# Surf5_R110.net
KiCad netlist of a schematic drawn in Altium Designer
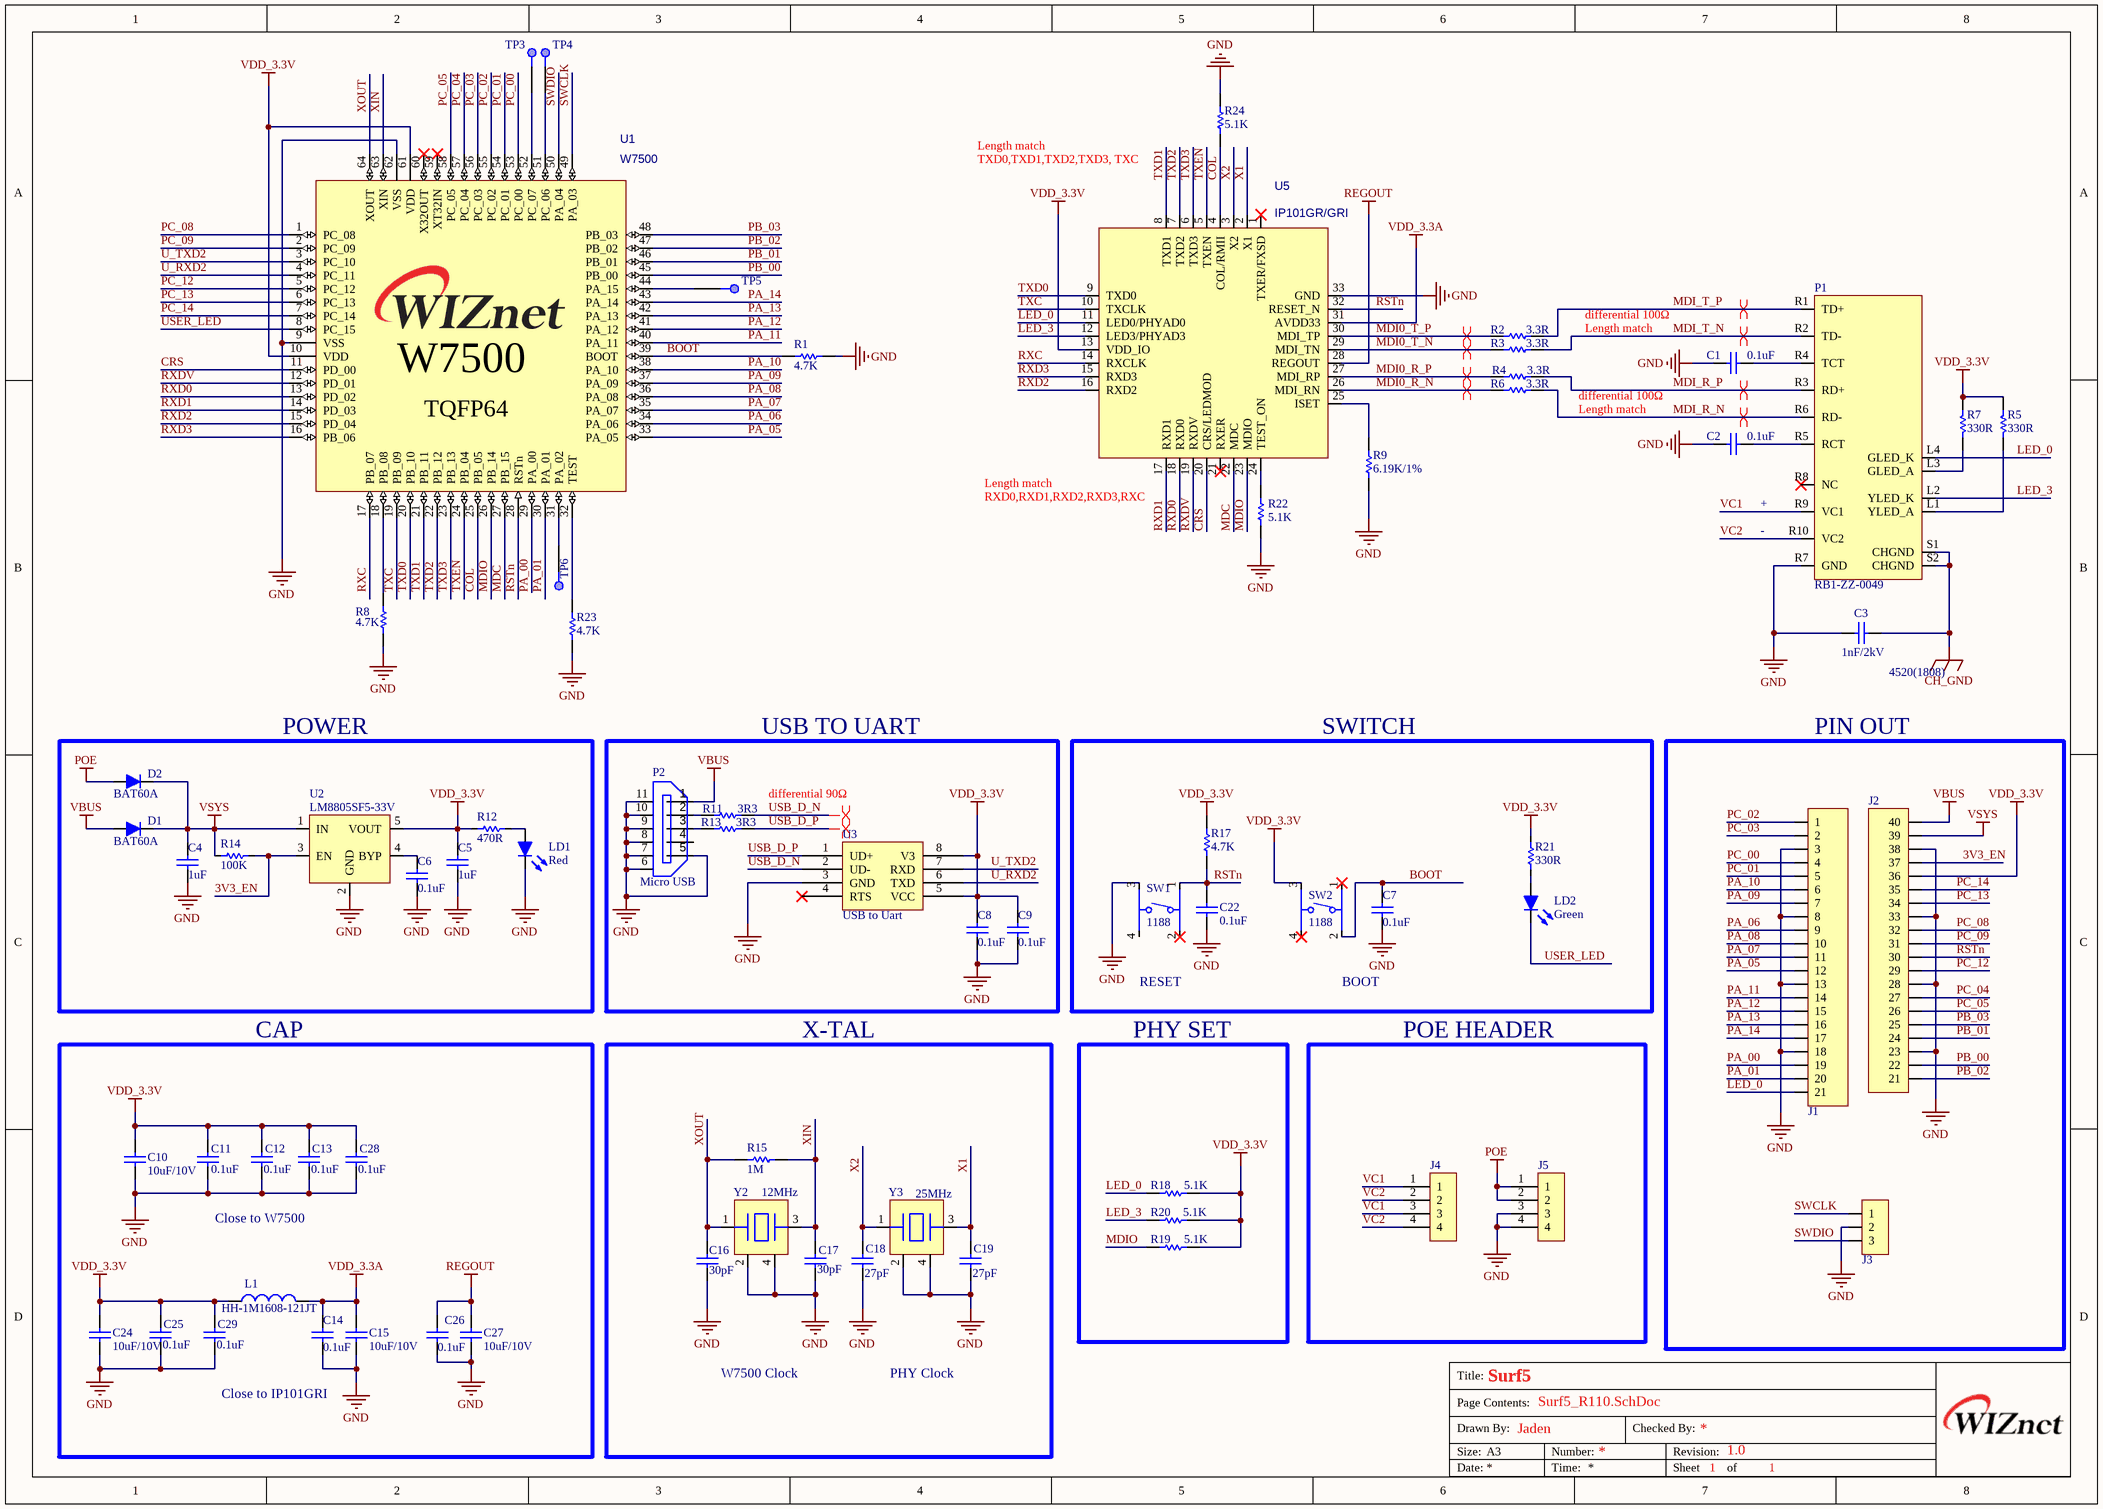
[diagram p0: Surf5_R110.SchDoc]

(export (version "E")
  (design (tool "Eeschema 10.0.6"))
  (components
    (comp (ref "C1")
      (value "0.1uF")
      (footprint "CAP-0402")
      (description "Ceramic CAP 0402(1005)")
      (libsource (lib "Scott_lib") (part "CAP-0402"))
    )
    (comp (ref "C2")
      (value "0.1uF")
      (footprint "CAP-0402")
      (description "Ceramic CAP 0402(1005)")
      (libsource (lib "Scott_lib") (part "CAP-0402"))
    )
    (comp (ref "C3")
      (value "1nF/2kV")
      (footprint "CAP-1808")
      (description "Ceramic CAP 1808(4520)")
      (libsource (lib "Scott_lib") (part "CAP-1808"))
    )
    (comp (ref "C4")
      (value "1uF")
      (footprint "CAP-0402")
      (description "Ceramic CAP 0402(1005)")
      (libsource (lib "Scott_lib") (part "CAP-0402"))
    )
    (comp (ref "C5")
      (value "1uF")
      (footprint "CAP-0402")
      (description "Ceramic CAP 0402(1005)")
      (libsource (lib "Scott_lib") (part "CAP-0402"))
    )
    (comp (ref "C6")
      (value "0.1uF")
      (footprint "CAP-0402")
      (description "Ceramic CAP 0402(1005)")
      (libsource (lib "Scott_lib") (part "CAP-0402"))
    )
    (comp (ref "C7")
      (value "0.1uF")
      (footprint "CAP-0402")
      (description "Ceramic CAP 0402(1005)")
      (libsource (lib "Scott_lib") (part "CAP-0402"))
    )
    (comp (ref "C8")
      (value "0.1uF")
      (footprint "CAP-0402")
      (description "Ceramic CAP 0402(1005)")
      (libsource (lib "Scott_lib") (part "CAP-0402"))
    )
    (comp (ref "C9")
      (value "0.1uF")
      (footprint "CAP-0402")
      (description "Ceramic CAP 0402(1005)")
      (libsource (lib "Scott_lib") (part "CAP-0402"))
    )
    (comp (ref "C10")
      (value "10uF/10V")
      (footprint "Surf5_R110:CAP-0805-3")
      (description "MLCC-0805(2012)")
      (libsource (lib "Surf5_R110") (part "CAP-0805"))
    )
    (comp (ref "C11")
      (value "0.1uF")
      (footprint "CAP-0402")
      (description "Ceramic CAP 0402(1005)")
      (libsource (lib "Scott_lib") (part "CAP-0402"))
    )
    (comp (ref "C12")
      (value "0.1uF")
      (footprint "CAP-0402")
      (description "Ceramic CAP 0402(1005)")
      (libsource (lib "Scott_lib") (part "CAP-0402"))
    )
    (comp (ref "C13")
      (value "0.1uF")
      (footprint "CAP-0402")
      (description "Ceramic CAP 0402(1005)")
      (libsource (lib "Scott_lib") (part "CAP-0402"))
    )
    (comp (ref "C14")
      (value "0.1uF")
      (footprint "CAP-0402")
      (description "Ceramic CAP 0402(1005)")
      (libsource (lib "Scott_lib") (part "CAP-0402"))
    )
    (comp (ref "C15")
      (value "10uF/10V")
      (footprint "Surf5_R110:CAP-0805-3")
      (description "MLCC-0805(2012)")
      (libsource (lib "Surf5_R110") (part "CAP-0805"))
    )
    (comp (ref "C16")
      (value "30pF")
      (footprint "CAP-0402")
      (description "Ceramic CAP 0402(1005)")
      (libsource (lib "Scott_lib") (part "CAP-0402"))
    )
    (comp (ref "C17")
      (value "30pF")
      (footprint "CAP-0402")
      (description "Ceramic CAP 0402(1005)")
      (libsource (lib "Scott_lib") (part "CAP-0402"))
    )
    (comp (ref "C18")
      (value "27pF")
      (footprint "CAP-0402")
      (description "Ceramic CAP 0402(1005)")
      (libsource (lib "Scott_lib") (part "CAP-0402"))
    )
    (comp (ref "C19")
      (value "27pF")
      (footprint "CAP-0402")
      (description "Ceramic CAP 0402(1005)")
      (libsource (lib "Scott_lib") (part "CAP-0402"))
    )
    (comp (ref "C22")
      (value "0.1uF")
      (footprint "CAP-0402")
      (description "Ceramic CAP 0402(1005)")
      (libsource (lib "Scott_lib") (part "CAP-0402"))
    )
    (comp (ref "C24")
      (value "10uF/10V")
      (footprint "Surf5_R110:CAP-0805-3")
      (description "MLCC-0805(2012)")
      (libsource (lib "Surf5_R110") (part "CAP-0805"))
    )
    (comp (ref "C25")
      (value "0.1uF")
      (footprint "CAP-0402")
      (description "Ceramic CAP 0402(1005)")
      (libsource (lib "Scott_lib") (part "CAP-0402"))
    )
    (comp (ref "C26")
      (value "0.1uF")
      (footprint "CAP-0402")
      (description "Ceramic CAP 0402(1005)")
      (libsource (lib "Scott_lib") (part "CAP-0402"))
    )
    (comp (ref "C27")
      (value "10uF/10V")
      (footprint "Surf5_R110:CAP-0805-3")
      (description "MLCC-0805(2012)")
      (libsource (lib "Surf5_R110") (part "CAP-0805"))
    )
    (comp (ref "C28")
      (value "0.1uF")
      (footprint "CAP-0402")
      (description "Ceramic CAP 0402(1005)")
      (libsource (lib "Scott_lib") (part "CAP-0402"))
    )
    (comp (ref "C29")
      (value "0.1uF")
      (footprint "CAP-0402")
      (description "Ceramic CAP 0402(1005)")
      (libsource (lib "Scott_lib") (part "CAP-0402"))
    )
    (comp (ref "D1")
      (value "BAT60A")
      (footprint "SOD-323(1-C,2-A)")
      (description "Silicon Schottky Diode")
      (libsource (lib "Scott_lib") (part "DIODE-BAT60A"))
    )
    (comp (ref "D2")
      (value "BAT60A")
      (footprint "SOD-323(1-C,2-A)")
      (description "Silicon Schottky Diode")
      (libsource (lib "Scott_lib") (part "DIODE-BAT60A"))
    )
    (comp (ref "J1")
      (value "2.54mm 1x21 Pin Header DIP")
      (footprint "IDC-1X21")
      (libsource (lib "Surf5") (part "2.54mm 1x21 Pin Header DIP"))
    )
    (comp (ref "J2")
      (value "2.54mm 1x20 Pin Header DIP")
      (footprint "IDC-1X20")
      (libsource (lib "Scott_lib") (part "2.54mm 1x20 Pin Header DIP"))
    )
    (comp (ref "J3")
      (value "2.54mm 1x3 Pin Header DIP")
      (footprint "IDC-1X3")
      (libsource (lib "Alan_Lib") (part "2.54mm 1x3 Pin Header DIP"))
    )
    (comp (ref "J4")
      (value "Header Socket 1x4_2.54mm")
      (footprint "Surf5_R110:Header-Socket(DIP)_4x1_2.54mm")
      (description "Connector")
      (fields
        (field (name "MANUFACTURER_PART_NUMBER") "M20-7820442")
        (field (name "MOUSER PART NUMBER") "855-M20-7820442")
      )
      (libsource (lib "Surf5_R110") (part "Header Socket 1x4_2.54mm"))
    )
    (comp (ref "J5")
      (value "Header Socket 1x4_2.54mm")
      (footprint "Surf5_R110:Header-Socket(DIP)_4x1_2.54mm")
      (description "Connector")
      (fields
        (field (name "MANUFACTURER_PART_NUMBER") "M20-7820442")
        (field (name "MOUSER PART NUMBER") "855-M20-7820442")
      )
      (libsource (lib "Surf5_R110") (part "Header Socket 1x4_2.54mm"))
    )
    (comp (ref "L1")
      (value "HH-1M1608-121JT")
      (footprint "IND-0603")
      (description "Inductor 0603(1608)")
      (libsource (lib "Scott_lib") (part "IND-0603"))
    )
    (comp (ref "LD1")
      (value "Red")
      (footprint "LED-0603-RED")
      (description "LED-0603")
      (libsource (lib "Scott_lib") (part "LED-0603"))
    )
    (comp (ref "LD2")
      (value "Green")
      (footprint "LED-0603-RED")
      (description "LED-0603")
      (libsource (lib "Scott_lib") (part "LED-0603"))
    )
    (comp (ref "P1")
      (value "RB1-ZZ-0049")
      (footprint "Surf5_R110:RB1-ZZ-0049")
      (description "PoE RJ45")
      (libsource (lib "Surf5_R110") (part "RB1-ZZ-0049"))
    )
    (comp (ref "P2")
      (value "Micro USB")
      (footprint "Micro 5P B DBX 6.4")
      (description "Micro USB B Connector SMD")
      (libsource (lib "Scott_lib") (part "Micro USB 5P DBX6.4"))
    )
    (comp (ref "R1")
      (value "4.7K")
      (footprint "RES-0402")
      (description "RES-0402")
      (libsource (lib "Scott_lib") (part "RES-0402"))
    )
    (comp (ref "R2")
      (value "3.3R")
      (footprint "RES-0402")
      (description "RES-0402")
      (libsource (lib "Scott_lib") (part "RES-0402"))
    )
    (comp (ref "R3")
      (value "3.3R")
      (footprint "RES-0402")
      (description "RES-0402")
      (libsource (lib "Scott_lib") (part "RES-0402"))
    )
    (comp (ref "R4")
      (value "3.3R")
      (footprint "RES-0402")
      (description "RES-0402")
      (libsource (lib "Scott_lib") (part "RES-0402"))
    )
    (comp (ref "R5")
      (value "330R")
      (footprint "RES-0402")
      (description "RES-0402")
      (libsource (lib "Scott_lib") (part "RES-0402"))
    )
    (comp (ref "R6")
      (value "3.3R")
      (footprint "RES-0402")
      (description "RES-0402")
      (libsource (lib "Scott_lib") (part "RES-0402"))
    )
    (comp (ref "R7")
      (value "330R")
      (footprint "RES-0402")
      (description "RES-0402")
      (libsource (lib "Scott_lib") (part "RES-0402"))
    )
    (comp (ref "R8")
      (value "4.7K")
      (footprint "RES-0402")
      (description "RES-0402")
      (libsource (lib "Scott_lib") (part "RES-0402"))
    )
    (comp (ref "R9")
      (value "6.19K/1%")
      (footprint "RES-0402")
      (description "RES-0402")
      (libsource (lib "Scott_lib") (part "RES-0402"))
    )
    (comp (ref "R11")
      (value "3R3")
      (footprint "RES-0402")
      (description "RES-0402")
      (libsource (lib "Scott_lib") (part "RES-0402"))
    )
    (comp (ref "R12")
      (value "470R")
      (footprint "RES-0402")
      (description "RES-0402")
      (libsource (lib "") (part "RES-0402_1"))
    )
    (comp (ref "R13")
      (value "3R3")
      (footprint "RES-0402")
      (description "RES-0402")
      (libsource (lib "Scott_lib") (part "RES-0402"))
    )
    (comp (ref "R14")
      (value "100K")
      (footprint "RES-0402")
      (description "RES-0402")
      (libsource (lib "") (part "RES-0402_1"))
    )
    (comp (ref "R15")
      (value "1M")
      (footprint "RES-0402")
      (description "RES-0402")
      (libsource (lib "Scott_lib") (part "RES-0402"))
    )
    (comp (ref "R17")
      (value "4.7K")
      (footprint "RES-0402")
      (description "RES-0402")
      (libsource (lib "Scott_lib") (part "RES-0402"))
    )
    (comp (ref "R18")
      (value "5.1K")
      (footprint "RES-0402")
      (description "RES-0402")
      (libsource (lib "Scott_lib") (part "RES-0402"))
    )
    (comp (ref "R19")
      (value "5.1K")
      (footprint "RES-0402")
      (description "RES-0402")
      (libsource (lib "Scott_lib") (part "RES-0402"))
    )
    (comp (ref "R20")
      (value "5.1K")
      (footprint "RES-0402")
      (description "RES-0402")
      (libsource (lib "Scott_lib") (part "RES-0402"))
    )
    (comp (ref "R21")
      (value "330R")
      (footprint "RES-0402")
      (description "RES-0402")
      (libsource (lib "") (part "RES-0402_1"))
    )
    (comp (ref "R22")
      (value "5.1K")
      (footprint "RES-0402")
      (description "RES-0402")
      (libsource (lib "Scott_lib") (part "RES-0402"))
    )
    (comp (ref "R23")
      (value "4.7K")
      (footprint "RES-0402")
      (description "RES-0402")
      (libsource (lib "Scott_lib") (part "RES-0402"))
    )
    (comp (ref "R24")
      (value "5.1K")
      (footprint "RES-0402")
      (description "RES-0402")
      (libsource (lib "Scott_lib") (part "RES-0402"))
    )
    (comp (ref "SW1")
      (value "1188")
      (footprint "SamacSys:TS204225WT160SMTTR")
      (description "Switch")
      (fields
        (field (name "MANUFACTURER_PART_NUMBER") "TS20-42-25-WT-160-SMT-TR")
        (field (name "MOUSER PART NUMBER") "179-TS204225WT160SMT")
      )
      (libsource (lib "Surf5") (part "1188"))
    )
    (comp (ref "SW2")
      (value "1188")
      (footprint "SamacSys:TS204225WT160SMTTR")
      (description "Switch")
      (fields
        (field (name "MANUFACTURER_PART_NUMBER") "TS20-42-25-WT-160-SMT-TR")
        (field (name "MOUSER PART NUMBER") "179-TS204225WT160SMT")
      )
      (libsource (lib "Surf5") (part "1188"))
    )
    (comp (ref "TP3")
      (value "TPS")
      (footprint "Surf5_R110:TPS")
      (description "Test_point")
      (fields
        (field (name "MANUFACTURER") "Wurth Elektronik")
        (field (name "PART NUMBER") "61300211121")
        (field (name "PUBLISHER") "WurthElektronik")
      )
      (libsource (lib "Surf5_R110") (part "TPS"))
    )
    (comp (ref "TP4")
      (value "TPS")
      (footprint "Surf5_R110:TPS")
      (description "Test_point")
      (fields
        (field (name "MANUFACTURER") "Wurth Elektronik")
        (field (name "PART NUMBER") "61300211121")
        (field (name "PUBLISHER") "WurthElektronik")
      )
      (libsource (lib "Surf5_R110") (part "TPS"))
    )
    (comp (ref "TP5")
      (value "TPS")
      (footprint "Surf5_R110:TPS")
      (description "Test_point")
      (fields
        (field (name "MANUFACTURER") "Wurth Elektronik")
        (field (name "PART NUMBER") "61300211121")
        (field (name "PUBLISHER") "WurthElektronik")
      )
      (libsource (lib "Surf5_R110") (part "TPS"))
    )
    (comp (ref "TP6")
      (value "TPS")
      (footprint "Surf5_R110:TPS")
      (description "Test_point")
      (fields
        (field (name "MANUFACTURER") "Wurth Elektronik")
        (field (name "PART NUMBER") "61300211121")
        (field (name "PUBLISHER") "WurthElektronik")
      )
      (libsource (lib "Surf5_R110") (part "TPS"))
    )
    (comp (ref "U1")
      (value "W7500")
      (footprint "Surf5_R110:W7500-LQFP64")
      (description "WIZnet ARM Cortex-M0")
      (libsource (lib "Surf5_R110") (part "W7500"))
    )
    (comp (ref "U2")
      (value "LM8805SF5-33V")
      (footprint "SOT-23-5L")
      (description "600mA CMOS LDO Regulator")
      (libsource (lib "Scott_lib") (part "LM8805SF5-33V"))
    )
    (comp (ref "U3") (value "USB to Uart") (footprint "CH340N") (libsource (lib "Jaden_Lib") (part "CH340N")))
    (comp (ref "U5")
      (value "IP101GR/GRI")
      (footprint "Surf5_R110:QFN32(0.4/4X4)")
      (libsource (lib "Surf5_R110") (part "IP101GR/GRI"))
    )
    (comp (ref "Y2")
      (value "12MHz")
      (footprint "OSC-TZ1067B")
      (description "X-tal 12MHz,3.2x2.5 SMD, CL=20pF")
      (libsource (lib "Scott_lib") (part "OSC-TZ1067B-12MHz"))
    )
    (comp (ref "Y3")
      (value "25MHz")
      (footprint "OSC-82J0626")
      (description "X-tal 25MHz,3.2x2.5 SMD, CL=18pF")
      (libsource (lib "Scott_lib") (part "OSC-82J0626-25MHz"))
    )
  )
  (nets
    (net (code "1") (name "/3V3_EN") (class "Default")
      (node (ref "J2") (pin "17") (pinfunction "37_17") (pintype "passive"))
      (node (ref "R14") (pin "2") (pinfunction "2_2") (pintype "passive"))
      (node (ref "U2") (pin "3") (pinfunction "EN_3") (pintype "power_in"))
    )
    (net (code "2") (name "/BOOT") (class "Default")
      (node (ref "C7") (pin "2") (pinfunction "2_2") (pintype "passive"))
      (node (ref "R1") (pin "2") (pinfunction "2_2") (pintype "passive"))
      (node (ref "SW2") (pin "2") (pinfunction "2_2") (pintype "passive"))
      (node (ref "U1") (pin "39") (pinfunction "BOOT_39") (pintype "bidirectional"))
    )
    (net (code "3") (name "/COL") (class "Default")
      (node (ref "R24") (pin "1") (pinfunction "1_1") (pintype "passive"))
      (node (ref "U1") (pin "25") (pinfunction "PB_05_25") (pintype "bidirectional"))
      (node (ref "U5") (pin "4") (pinfunction "COL/RMII_4") (pintype "passive"))
    )
    (net (code "4") (name "/CRS") (class "Default")
      (node (ref "U1") (pin "11") (pinfunction "PD_00_11") (pintype "bidirectional"))
      (node (ref "U5") (pin "20") (pinfunction "CRS/LEDMOD_20") (pintype "passive"))
    )
    (net (code "5") (name "/LED_0") (class "Default")
      (node (ref "J1") (pin "21") (pinfunction "21_21") (pintype "passive"))
      (node (ref "P1") (pin "L4") (pinfunction "GLED_K_L4") (pintype "passive"))
      (node (ref "R18") (pin "1") (pinfunction "1_1") (pintype "passive"))
      (node (ref "U5") (pin "11") (pinfunction "LED0/PHYAD0_11") (pintype "passive"))
    )
    (net (code "6") (name "/LED_3") (class "Default")
      (node (ref "P1") (pin "L2") (pinfunction "YLED_K_L2") (pintype "passive"))
      (node (ref "R20") (pin "1") (pinfunction "1_1") (pintype "passive"))
      (node (ref "U5") (pin "12") (pinfunction "LED3/PHYAD3_12") (pintype "passive"))
    )
    (net (code "7") (name "/MDC") (class "Default")
      (node (ref "U1") (pin "27") (pinfunction "PB_15_27") (pintype "bidirectional"))
      (node (ref "U5") (pin "22") (pinfunction "MDC_22") (pintype "passive"))
    )
    (net (code "8") (name "/MDI0_R_N") (class "Default")
      (node (ref "R6") (pin "1") (pinfunction "1_1") (pintype "passive"))
      (node (ref "U5") (pin "26") (pinfunction "MDI_RN_26") (pintype "passive"))
    )
    (net (code "9") (name "/MDI0_R_P") (class "Default")
      (node (ref "R4") (pin "1") (pinfunction "1_1") (pintype "passive"))
      (node (ref "U5") (pin "27") (pinfunction "MDI_RP_27") (pintype "passive"))
    )
    (net (code "10") (name "/MDI0_T_N") (class "Default")
      (node (ref "R3") (pin "1") (pinfunction "1_1") (pintype "passive"))
      (node (ref "U5") (pin "29") (pinfunction "MDI_TN_29") (pintype "passive"))
    )
    (net (code "11") (name "/MDI0_T_P") (class "Default")
      (node (ref "R2") (pin "1") (pinfunction "1_1") (pintype "passive"))
      (node (ref "U5") (pin "30") (pinfunction "MDI_TP_30") (pintype "passive"))
    )
    (net (code "12") (name "/MDIO") (class "Default")
      (node (ref "R19") (pin "1") (pinfunction "1_1") (pintype "passive"))
      (node (ref "U1") (pin "26") (pinfunction "PB_14_26") (pintype "bidirectional"))
      (node (ref "U5") (pin "23") (pinfunction "MDIO_23") (pintype "passive"))
    )
    (net (code "13") (name "/MDI_R_N") (class "Default")
      (node (ref "P1") (pin "R6") (pinfunction "RD-_R6") (pintype "passive"))
      (node (ref "R6") (pin "2") (pinfunction "2_2") (pintype "passive"))
    )
    (net (code "14") (name "/MDI_R_P") (class "Default")
      (node (ref "P1") (pin "R3") (pinfunction "RD+_R3") (pintype "passive"))
      (node (ref "R4") (pin "2") (pinfunction "2_2") (pintype "passive"))
    )
    (net (code "15") (name "/MDI_T_N") (class "Default")
      (node (ref "P1") (pin "R2") (pinfunction "TD-_R2") (pintype "passive"))
      (node (ref "R3") (pin "2") (pinfunction "2_2") (pintype "passive"))
    )
    (net (code "16") (name "/MDI_T_P") (class "Default")
      (node (ref "P1") (pin "R1") (pinfunction "TD+_R1") (pintype "passive"))
      (node (ref "R2") (pin "2") (pinfunction "2_2") (pintype "passive"))
    )
    (net (code "17") (name "/PA_00") (class "Default")
      (node (ref "J1") (pin "19") (pinfunction "19_19") (pintype "passive"))
      (node (ref "U1") (pin "29") (pinfunction "PA_00_29") (pintype "bidirectional"))
    )
    (net (code "18") (name "/PA_01") (class "Default")
      (node (ref "J1") (pin "20") (pinfunction "20_20") (pintype "passive"))
      (node (ref "U1") (pin "30") (pinfunction "PA_01_30") (pintype "bidirectional"))
    )
    (net (code "19") (name "/PA_05") (class "Default")
      (node (ref "J1") (pin "12") (pinfunction "12_12") (pintype "passive"))
      (node (ref "U1") (pin "33") (pinfunction "PA_05_33") (pintype "bidirectional"))
    )
    (net (code "20") (name "/PA_06") (class "Default")
      (node (ref "J1") (pin "9") (pinfunction "9_9") (pintype "passive"))
      (node (ref "U1") (pin "34") (pinfunction "PA_06_34") (pintype "bidirectional"))
    )
    (net (code "21") (name "/PA_07") (class "Default")
      (node (ref "J1") (pin "11") (pinfunction "11_11") (pintype "passive"))
      (node (ref "U1") (pin "35") (pinfunction "PA_07_35") (pintype "bidirectional"))
    )
    (net (code "22") (name "/PA_08") (class "Default")
      (node (ref "J1") (pin "10") (pinfunction "10_10") (pintype "passive"))
      (node (ref "U1") (pin "36") (pinfunction "PA_08_36") (pintype "bidirectional"))
    )
    (net (code "23") (name "/PA_09") (class "Default")
      (node (ref "J1") (pin "7") (pinfunction "7_7") (pintype "passive"))
      (node (ref "U1") (pin "37") (pinfunction "PA_09_37") (pintype "bidirectional"))
    )
    (net (code "24") (name "/PA_10") (class "Default")
      (node (ref "J1") (pin "6") (pinfunction "6_6") (pintype "passive"))
      (node (ref "U1") (pin "38") (pinfunction "PA_10_38") (pintype "bidirectional"))
    )
    (net (code "25") (name "/PA_11") (class "Default")
      (node (ref "J1") (pin "14") (pinfunction "14_14") (pintype "passive"))
      (node (ref "U1") (pin "40") (pinfunction "PA_11_40") (pintype "bidirectional"))
    )
    (net (code "26") (name "/PA_12") (class "Default")
      (node (ref "J1") (pin "15") (pinfunction "15_15") (pintype "passive"))
      (node (ref "U1") (pin "41") (pinfunction "PA_12_41") (pintype "bidirectional"))
    )
    (net (code "27") (name "/PA_13") (class "Default")
      (node (ref "J1") (pin "16") (pinfunction "16_16") (pintype "passive"))
      (node (ref "U1") (pin "42") (pinfunction "PA_13_42") (pintype "bidirectional"))
    )
    (net (code "28") (name "/PA_14") (class "Default")
      (node (ref "J1") (pin "17") (pinfunction "17_17") (pintype "passive"))
      (node (ref "U1") (pin "43") (pinfunction "PA_14_43") (pintype "bidirectional"))
    )
    (net (code "29") (name "/PB_00") (class "Default")
      (node (ref "J2") (pin "2") (pinfunction "22_2") (pintype "passive"))
      (node (ref "U1") (pin "45") (pinfunction "PB_00_45") (pintype "bidirectional"))
    )
    (net (code "30") (name "/PB_01") (class "Default")
      (node (ref "J2") (pin "4") (pinfunction "24_4") (pintype "passive"))
      (node (ref "U1") (pin "46") (pinfunction "PB_01_46") (pintype "bidirectional"))
    )
    (net (code "31") (name "/PB_02") (class "Default")
      (node (ref "J2") (pin "1") (pinfunction "21_1") (pintype "passive"))
      (node (ref "U1") (pin "47") (pinfunction "PB_02_47") (pintype "bidirectional"))
    )
    (net (code "32") (name "/PB_03") (class "Default")
      (node (ref "J2") (pin "5") (pinfunction "25_5") (pintype "passive"))
      (node (ref "U1") (pin "48") (pinfunction "PB_03_48") (pintype "bidirectional"))
    )
    (net (code "33") (name "/PC_00") (class "Default")
      (node (ref "J1") (pin "4") (pinfunction "4_4") (pintype "passive"))
      (node (ref "U1") (pin "53") (pinfunction "PC_00_53") (pintype "bidirectional"))
    )
    (net (code "34") (name "/PC_01") (class "Default")
      (node (ref "J1") (pin "5") (pinfunction "5_5") (pintype "passive"))
      (node (ref "U1") (pin "54") (pinfunction "PC_01_54") (pintype "bidirectional"))
    )
    (net (code "35") (name "/PC_02") (class "Default")
      (node (ref "J1") (pin "1") (pinfunction "1_1") (pintype "passive"))
      (node (ref "U1") (pin "55") (pinfunction "PC_02_55") (pintype "bidirectional"))
    )
    (net (code "36") (name "/PC_03") (class "Default")
      (node (ref "J1") (pin "2") (pinfunction "2_2") (pintype "passive"))
      (node (ref "U1") (pin "56") (pinfunction "PC_03_56") (pintype "bidirectional"))
    )
    (net (code "37") (name "/PC_04") (class "Default")
      (node (ref "J2") (pin "7") (pinfunction "27_7") (pintype "passive"))
      (node (ref "U1") (pin "57") (pinfunction "PC_04_57") (pintype "bidirectional"))
    )
    (net (code "38") (name "/PC_05") (class "Default")
      (node (ref "J2") (pin "6") (pinfunction "26_6") (pintype "passive"))
      (node (ref "U1") (pin "58") (pinfunction "PC_05_58") (pintype "bidirectional"))
    )
    (net (code "39") (name "/PC_08") (class "Default")
      (node (ref "J2") (pin "12") (pinfunction "32_12") (pintype "passive"))
      (node (ref "U1") (pin "1") (pinfunction "PC_08_1") (pintype "bidirectional"))
    )
    (net (code "40") (name "/PC_09") (class "Default")
      (node (ref "J2") (pin "11") (pinfunction "31_11") (pintype "passive"))
      (node (ref "U1") (pin "2") (pinfunction "PC_09_2") (pintype "bidirectional"))
    )
    (net (code "41") (name "/PC_12") (class "Default")
      (node (ref "J2") (pin "9") (pinfunction "29_9") (pintype "passive"))
      (node (ref "U1") (pin "5") (pinfunction "PC_12_5") (pintype "bidirectional"))
    )
    (net (code "42") (name "/PC_13") (class "Default")
      (node (ref "J2") (pin "14") (pinfunction "34_14") (pintype "passive"))
      (node (ref "U1") (pin "6") (pinfunction "PC_13_6") (pintype "bidirectional"))
    )
    (net (code "43") (name "/PC_14") (class "Default")
      (node (ref "J2") (pin "15") (pinfunction "35_15") (pintype "passive"))
      (node (ref "U1") (pin "7") (pinfunction "PC_14_7") (pintype "bidirectional"))
    )
    (net (code "44") (name "/RSTn") (class "Default")
      (node (ref "C22") (pin "1") (pinfunction "1_1") (pintype "passive"))
      (node (ref "J2") (pin "10") (pinfunction "30_10") (pintype "passive"))
      (node (ref "R17") (pin "2") (pinfunction "2_2") (pintype "passive"))
      (node (ref "SW1") (pin "1") (pinfunction "1_1") (pintype "passive"))
      (node (ref "U1") (pin "28") (pinfunction "RSTn_28") (pintype "input"))
      (node (ref "U5") (pin "32") (pinfunction "RESET_N_32") (pintype "passive"))
    )
    (net (code "45") (name "/RXC") (class "Default")
      (node (ref "U1") (pin "17") (pinfunction "PB_07_17") (pintype "bidirectional"))
      (node (ref "U5") (pin "14") (pinfunction "RXCLK_14") (pintype "passive"))
    )
    (net (code "46") (name "/RXD0") (class "Default")
      (node (ref "U1") (pin "13") (pinfunction "PD_02_13") (pintype "bidirectional"))
      (node (ref "U5") (pin "18") (pinfunction "RXD0_18") (pintype "passive"))
    )
    (net (code "47") (name "/RXD1") (class "Default")
      (node (ref "U1") (pin "14") (pinfunction "PD_03_14") (pintype "bidirectional"))
      (node (ref "U5") (pin "17") (pinfunction "RXD1_17") (pintype "passive"))
    )
    (net (code "48") (name "/RXD2") (class "Default")
      (node (ref "U1") (pin "15") (pinfunction "PD_04_15") (pintype "bidirectional"))
      (node (ref "U5") (pin "16") (pinfunction "RXD2_16") (pintype "passive"))
    )
    (net (code "49") (name "/RXD3") (class "Default")
      (node (ref "U1") (pin "16") (pinfunction "PB_06_16") (pintype "bidirectional"))
      (node (ref "U5") (pin "15") (pinfunction "RXD3_15") (pintype "passive"))
    )
    (net (code "50") (name "/RXDV") (class "Default")
      (node (ref "U1") (pin "12") (pinfunction "PD_01_12") (pintype "bidirectional"))
      (node (ref "U5") (pin "19") (pinfunction "RXDV_19") (pintype "passive"))
    )
    (net (code "51") (name "/SWCLK") (class "Default")
      (node (ref "J3") (pin "1") (pinfunction "1_1") (pintype "passive"))
      (node (ref "U1") (pin "49") (pinfunction "PA_03_49") (pintype "bidirectional"))
    )
    (net (code "52") (name "/SWDIO") (class "Default")
      (node (ref "J3") (pin "3") (pinfunction "3_3") (pintype "passive"))
      (node (ref "U1") (pin "50") (pinfunction "PA_04_50") (pintype "bidirectional"))
    )
    (net (code "53") (name "/TXC") (class "Default")
      (node (ref "U1") (pin "19") (pinfunction "PB_09_19") (pintype "bidirectional"))
      (node (ref "U5") (pin "10") (pinfunction "TXCLK_10") (pintype "passive"))
    )
    (net (code "54") (name "/TXD0") (class "Default")
      (node (ref "U1") (pin "20") (pinfunction "PB_10_20") (pintype "bidirectional"))
      (node (ref "U5") (pin "9") (pinfunction "TXD0_9") (pintype "passive"))
    )
    (net (code "55") (name "/TXD1") (class "Default")
      (node (ref "U1") (pin "21") (pinfunction "PB_11_21") (pintype "bidirectional"))
      (node (ref "U5") (pin "8") (pinfunction "TXD1_8") (pintype "passive"))
    )
    (net (code "56") (name "/TXD2") (class "Default")
      (node (ref "U1") (pin "22") (pinfunction "PB_12_22") (pintype "bidirectional"))
      (node (ref "U5") (pin "7") (pinfunction "TXD2_7") (pintype "passive"))
    )
    (net (code "57") (name "/TXD3") (class "Default")
      (node (ref "U1") (pin "23") (pinfunction "PB_13_23") (pintype "bidirectional"))
      (node (ref "U5") (pin "6") (pinfunction "TXD3_6") (pintype "passive"))
    )
    (net (code "58") (name "/TXEN") (class "Default")
      (node (ref "U1") (pin "24") (pinfunction "PB_04_24") (pintype "bidirectional"))
      (node (ref "U5") (pin "5") (pinfunction "TXEN_5") (pintype "passive"))
    )
    (net (code "59") (name "/USB_D_N") (class "Default")
      (node (ref "R11") (pin "2") (pinfunction "2_2") (pintype "passive"))
      (node (ref "U3") (pin "2") (pinfunction "UD-_2") (pintype "passive"))
    )
    (net (code "60") (name "/USB_D_P") (class "Default")
      (node (ref "R13") (pin "2") (pinfunction "2_2") (pintype "passive"))
      (node (ref "U3") (pin "1") (pinfunction "UD+_1") (pintype "passive"))
    )
    (net (code "61") (name "/USER_LED") (class "Default")
      (node (ref "LD2") (pin "2") (pinfunction "K_2") (pintype "passive"))
      (node (ref "U1") (pin "8") (pinfunction "PC_15_8") (pintype "bidirectional"))
    )
    (net (code "62") (name "/U_RXD2") (class "Default")
      (node (ref "U1") (pin "4") (pinfunction "PC_11_4") (pintype "bidirectional"))
      (node (ref "U3") (pin "6") (pinfunction "TXD_6") (pintype "passive"))
    )
    (net (code "63") (name "/U_TXD2") (class "Default")
      (node (ref "U1") (pin "3") (pinfunction "PC_10_3") (pintype "bidirectional"))
      (node (ref "U3") (pin "7") (pinfunction "RXD_7") (pintype "passive"))
    )
    (net (code "64") (name "/VC1") (class "Default")
      (node (ref "J4") (pin "1") (pinfunction "1_1") (pintype "passive"))
      (node (ref "J4") (pin "3") (pinfunction "3_3") (pintype "passive"))
      (node (ref "P1") (pin "R9") (pinfunction "VC1_R9") (pintype "passive"))
    )
    (net (code "65") (name "/VC2") (class "Default")
      (node (ref "J4") (pin "2") (pinfunction "2_2") (pintype "passive"))
      (node (ref "J4") (pin "4") (pinfunction "4_4") (pintype "passive"))
      (node (ref "P1") (pin "R10") (pinfunction "VC2_R10") (pintype "passive"))
    )
    (net (code "66") (name "/X1") (class "Default")
      (node (ref "C19") (pin "2") (pinfunction "2_2") (pintype "passive"))
      (node (ref "U5") (pin "2") (pinfunction "X1_2") (pintype "passive"))
      (node (ref "Y3") (pin "3") (pinfunction "3_3") (pintype "passive"))
    )
    (net (code "67") (name "/X2") (class "Default")
      (node (ref "C18") (pin "2") (pinfunction "2_2") (pintype "passive"))
      (node (ref "U5") (pin "3") (pinfunction "X2_3") (pintype "passive"))
      (node (ref "Y3") (pin "1") (pinfunction "1_1") (pintype "passive"))
    )
    (net (code "68") (name "/XIN") (class "Default")
      (node (ref "C17") (pin "2") (pinfunction "2_2") (pintype "passive"))
      (node (ref "R15") (pin "2") (pinfunction "2_2") (pintype "passive"))
      (node (ref "U1") (pin "63") (pinfunction "XIN_63") (pintype "bidirectional"))
      (node (ref "Y2") (pin "3") (pinfunction "3_3") (pintype "passive"))
    )
    (net (code "69") (name "/XOUT") (class "Default")
      (node (ref "C16") (pin "2") (pinfunction "2_2") (pintype "passive"))
      (node (ref "R15") (pin "1") (pinfunction "1_1") (pintype "passive"))
      (node (ref "U1") (pin "64") (pinfunction "XOUT_64") (pintype "bidirectional"))
      (node (ref "Y2") (pin "1") (pinfunction "1_1") (pintype "passive"))
    )
    (net (code "70") (name "CH_GND") (class "Default")
      (node (ref "C3") (pin "2") (pinfunction "2_2") (pintype "passive"))
      (node (ref "P1") (pin "S1") (pinfunction "CHGND_S1") (pintype "passive"))
      (node (ref "P1") (pin "S2") (pinfunction "CHGND_S2") (pintype "passive"))
    )
    (net (code "71") (name "GND") (class "Default")
      (node (ref "C1") (pin "1") (pinfunction "1_1") (pintype "passive"))
      (node (ref "C10") (pin "1") (pinfunction "1_1") (pintype "passive"))
      (node (ref "C11") (pin "1") (pinfunction "1_1") (pintype "passive"))
      (node (ref "C12") (pin "1") (pinfunction "1_1") (pintype "passive"))
      (node (ref "C13") (pin "1") (pinfunction "1_1") (pintype "passive"))
      (node (ref "C14") (pin "1") (pinfunction "1_1") (pintype "passive"))
      (node (ref "C15") (pin "1") (pinfunction "1_1") (pintype "passive"))
      (node (ref "C16") (pin "1") (pinfunction "1_1") (pintype "passive"))
      (node (ref "C17") (pin "1") (pinfunction "1_1") (pintype "passive"))
      (node (ref "C18") (pin "1") (pinfunction "1_1") (pintype "passive"))
      (node (ref "C19") (pin "1") (pinfunction "1_1") (pintype "passive"))
      (node (ref "C2") (pin "1") (pinfunction "1_1") (pintype "passive"))
      (node (ref "C22") (pin "2") (pinfunction "2_2") (pintype "passive"))
      (node (ref "C24") (pin "1") (pinfunction "1_1") (pintype "passive"))
      (node (ref "C25") (pin "1") (pinfunction "1_1") (pintype "passive"))
      (node (ref "C26") (pin "1") (pinfunction "1_1") (pintype "passive"))
      (node (ref "C27") (pin "1") (pinfunction "1_1") (pintype "passive"))
      (node (ref "C28") (pin "1") (pinfunction "1_1") (pintype "passive"))
      (node (ref "C29") (pin "1") (pinfunction "1_1") (pintype "passive"))
      (node (ref "C3") (pin "1") (pinfunction "1_1") (pintype "passive"))
      (node (ref "C4") (pin "1") (pinfunction "1_1") (pintype "passive"))
      (node (ref "C5") (pin "1") (pinfunction "1_1") (pintype "passive"))
      (node (ref "C6") (pin "1") (pinfunction "1_1") (pintype "passive"))
      (node (ref "C7") (pin "1") (pinfunction "1_1") (pintype "passive"))
      (node (ref "C8") (pin "1") (pinfunction "1_1") (pintype "passive"))
      (node (ref "C9") (pin "1") (pinfunction "1_1") (pintype "passive"))
      (node (ref "J1") (pin "13") (pinfunction "13_13") (pintype "passive"))
      (node (ref "J1") (pin "18") (pinfunction "18_18") (pintype "passive"))
      (node (ref "J1") (pin "3") (pinfunction "3_3") (pintype "passive"))
      (node (ref "J1") (pin "8") (pinfunction "8_8") (pintype "passive"))
      (node (ref "J2") (pin "13") (pinfunction "33_13") (pintype "passive"))
      (node (ref "J2") (pin "18") (pinfunction "38_18") (pintype "passive"))
      (node (ref "J2") (pin "3") (pinfunction "23_3") (pintype "passive"))
      (node (ref "J2") (pin "8") (pinfunction "28_8") (pintype "passive"))
      (node (ref "J3") (pin "2") (pinfunction "2_2") (pintype "passive"))
      (node (ref "J5") (pin "3") (pinfunction "3_3") (pintype "passive"))
      (node (ref "J5") (pin "4") (pinfunction "4_4") (pintype "passive"))
      (node (ref "LD1") (pin "2") (pinfunction "K_2") (pintype "passive"))
      (node (ref "P1") (pin "R7") (pinfunction "GND_R7") (pintype "passive"))
      (node (ref "P2") (pin "10") (pinfunction "10_10") (pintype "passive"))
      (node (ref "P2") (pin "11") (pinfunction "11_11") (pintype "passive"))
      (node (ref "P2") (pin "5") (pinfunction "5_5") (pintype "passive"))
      (node (ref "P2") (pin "6") (pinfunction "6_6") (pintype "passive"))
      (node (ref "P2") (pin "7") (pinfunction "7_7") (pintype "passive"))
      (node (ref "P2") (pin "8") (pinfunction "8_8") (pintype "passive"))
      (node (ref "P2") (pin "9") (pinfunction "9_9") (pintype "passive"))
      (node (ref "R1") (pin "1") (pinfunction "1_1") (pintype "passive"))
      (node (ref "R22") (pin "1") (pinfunction "1_1") (pintype "passive"))
      (node (ref "R23") (pin "2") (pinfunction "2_2") (pintype "passive"))
      (node (ref "R24") (pin "2") (pinfunction "2_2") (pintype "passive"))
      (node (ref "R8") (pin "1") (pinfunction "1_1") (pintype "passive"))
      (node (ref "R9") (pin "1") (pinfunction "1_1") (pintype "passive"))
      (node (ref "SW1") (pin "3") (pinfunction "3_3") (pintype "passive"))
      (node (ref "U1") (pin "62") (pinfunction "VSS_62") (pintype "power_in"))
      (node (ref "U1") (pin "9") (pinfunction "VSS_9") (pintype "power_in"))
      (node (ref "U2") (pin "2") (pinfunction "GND_2") (pintype "power_in"))
      (node (ref "U3") (pin "3") (pinfunction "GND_3") (pintype "passive"))
      (node (ref "U5") (pin "33") (pinfunction "GND_33") (pintype "passive"))
      (node (ref "Y2") (pin "2") (pinfunction "2_2") (pintype "passive"))
      (node (ref "Y2") (pin "4") (pinfunction "4_4") (pintype "passive"))
      (node (ref "Y3") (pin "2") (pinfunction "2_2") (pintype "passive"))
      (node (ref "Y3") (pin "4") (pinfunction "4_4") (pintype "passive"))
    )
    (net (code "72") (name "Net-(LD1-A)") (class "Default")
      (node (ref "LD1") (pin "1") (pinfunction "A_1") (pintype "passive"))
      (node (ref "R12") (pin "2") (pinfunction "2_2") (pintype "passive"))
    )
    (net (code "73") (name "Net-(LD2-A)") (class "Default")
      (node (ref "LD2") (pin "1") (pinfunction "A_1") (pintype "passive"))
      (node (ref "R21") (pin "1") (pinfunction "1_1") (pintype "passive"))
    )
    (net (code "74") (name "Net-(P1-GLED_A)") (class "Default")
      (node (ref "P1") (pin "L3") (pinfunction "GLED_A_L3") (pintype "passive"))
      (node (ref "R7") (pin "2") (pinfunction "2_2") (pintype "passive"))
    )
    (net (code "75") (name "Net-(P1-RCT)") (class "Default")
      (node (ref "C2") (pin "2") (pinfunction "2_2") (pintype "passive"))
      (node (ref "P1") (pin "R5") (pinfunction "RCT_R5") (pintype "passive"))
    )
    (net (code "76") (name "Net-(P1-TCT)") (class "Default")
      (node (ref "C1") (pin "2") (pinfunction "2_2") (pintype "passive"))
      (node (ref "P1") (pin "R4") (pinfunction "TCT_R4") (pintype "passive"))
    )
    (net (code "77") (name "Net-(P1-YLED_A)") (class "Default")
      (node (ref "P1") (pin "L1") (pinfunction "YLED_A_L1") (pintype "passive"))
      (node (ref "R5") (pin "2") (pinfunction "2_2") (pintype "passive"))
    )
    (net (code "78") (name "Net-(P2-Pad2)") (class "Default")
      (node (ref "P2") (pin "2") (pinfunction "2_2") (pintype "passive"))
      (node (ref "R11") (pin "1") (pinfunction "1_1") (pintype "passive"))
    )
    (net (code "79") (name "Net-(P2-Pad3)") (class "Default")
      (node (ref "P2") (pin "3") (pinfunction "3_3") (pintype "passive"))
      (node (ref "R13") (pin "1") (pinfunction "1_1") (pintype "passive"))
    )
    (net (code "80") (name "Net-(U1-PA_02)") (class "Default")
      (node (ref "TP6") (pin "1") (pinfunction "1_1") (pintype "passive"))
      (node (ref "U1") (pin "31") (pinfunction "PA_02_31") (pintype "bidirectional"))
    )
    (net (code "81") (name "Net-(U1-PA_15)") (class "Default")
      (node (ref "TP5") (pin "1") (pinfunction "1_1") (pintype "passive"))
      (node (ref "U1") (pin "44") (pinfunction "PA_15_44") (pintype "bidirectional"))
    )
    (net (code "82") (name "Net-(U1-PB_08)") (class "Default")
      (node (ref "R8") (pin "2") (pinfunction "2_2") (pintype "passive"))
      (node (ref "U1") (pin "18") (pinfunction "PB_08_18") (pintype "bidirectional"))
    )
    (net (code "83") (name "Net-(U1-PC_06)") (class "Default")
      (node (ref "TP4") (pin "1") (pinfunction "1_1") (pintype "passive"))
      (node (ref "U1") (pin "51") (pinfunction "PC_06_51") (pintype "bidirectional"))
    )
    (net (code "84") (name "Net-(U1-PC_07)") (class "Default")
      (node (ref "TP3") (pin "1") (pinfunction "1_1") (pintype "passive"))
      (node (ref "U1") (pin "52") (pinfunction "PC_07_52") (pintype "bidirectional"))
    )
    (net (code "85") (name "Net-(U1-TEST)") (class "Default")
      (node (ref "R23") (pin "1") (pinfunction "1_1") (pintype "passive"))
      (node (ref "U1") (pin "32") (pinfunction "TEST_32") (pintype "bidirectional"))
    )
    (net (code "86") (name "Net-(U2-BYP)") (class "Default")
      (node (ref "C6") (pin "2") (pinfunction "2_2") (pintype "passive"))
      (node (ref "U2") (pin "4") (pinfunction "BYP_4") (pintype "power_in"))
    )
    (net (code "87") (name "Net-(U5-ISET)") (class "Default")
      (node (ref "R9") (pin "2") (pinfunction "2_2") (pintype "passive"))
      (node (ref "U5") (pin "25") (pinfunction "ISET_25") (pintype "passive"))
    )
    (net (code "88") (name "Net-(U5-TEST_ON)") (class "Default")
      (node (ref "R22") (pin "2") (pinfunction "2_2") (pintype "passive"))
      (node (ref "U5") (pin "24") (pinfunction "TEST_ON_24") (pintype "passive"))
    )
    (net (code "89") (name "POE") (class "Default")
      (node (ref "D2") (pin "2") (pinfunction "A_2") (pintype "passive"))
      (node (ref "J5") (pin "1") (pinfunction "1_1") (pintype "passive"))
      (node (ref "J5") (pin "2") (pinfunction "2_2") (pintype "passive"))
    )
    (net (code "90") (name "REGOUT") (class "Default")
      (node (ref "C26") (pin "2") (pinfunction "2_2") (pintype "passive"))
      (node (ref "C27") (pin "2") (pinfunction "2_2") (pintype "passive"))
      (node (ref "U5") (pin "28") (pinfunction "REGOUT_28") (pintype "passive"))
    )
    (net (code "91") (name "VBUS") (class "Default")
      (node (ref "D1") (pin "2") (pinfunction "A_2") (pintype "passive"))
      (node (ref "J2") (pin "20") (pinfunction "40_20") (pintype "passive"))
      (node (ref "P2") (pin "1") (pinfunction "1_1") (pintype "passive"))
    )
    (net (code "92") (name "VDD_3.3A") (class "Default")
      (node (ref "C14") (pin "2") (pinfunction "2_2") (pintype "passive"))
      (node (ref "C15") (pin "2") (pinfunction "2_2") (pintype "passive"))
      (node (ref "L1") (pin "2") (pinfunction "2_2") (pintype "passive"))
      (node (ref "U5") (pin "31") (pinfunction "AVDD33_31") (pintype "passive"))
    )
    (net (code "93") (name "VDD_3.3V") (class "Default")
      (node (ref "C10") (pin "2") (pinfunction "2_2") (pintype "passive"))
      (node (ref "C11") (pin "2") (pinfunction "2_2") (pintype "passive"))
      (node (ref "C12") (pin "2") (pinfunction "2_2") (pintype "passive"))
      (node (ref "C13") (pin "2") (pinfunction "2_2") (pintype "passive"))
      (node (ref "C24") (pin "2") (pinfunction "2_2") (pintype "passive"))
      (node (ref "C25") (pin "2") (pinfunction "2_2") (pintype "passive"))
      (node (ref "C28") (pin "2") (pinfunction "2_2") (pintype "passive"))
      (node (ref "C29") (pin "2") (pinfunction "2_2") (pintype "passive"))
      (node (ref "C5") (pin "2") (pinfunction "2_2") (pintype "passive"))
      (node (ref "C8") (pin "2") (pinfunction "2_2") (pintype "passive"))
      (node (ref "C9") (pin "2") (pinfunction "2_2") (pintype "passive"))
      (node (ref "J2") (pin "16") (pinfunction "36_16") (pintype "passive"))
      (node (ref "L1") (pin "1") (pinfunction "1_1") (pintype "passive"))
      (node (ref "R12") (pin "1") (pinfunction "1_1") (pintype "passive"))
      (node (ref "R17") (pin "1") (pinfunction "1_1") (pintype "passive"))
      (node (ref "R18") (pin "2") (pinfunction "2_2") (pintype "passive"))
      (node (ref "R19") (pin "2") (pinfunction "2_2") (pintype "passive"))
      (node (ref "R20") (pin "2") (pinfunction "2_2") (pintype "passive"))
      (node (ref "R21") (pin "2") (pinfunction "2_2") (pintype "passive"))
      (node (ref "R5") (pin "1") (pinfunction "1_1") (pintype "passive"))
      (node (ref "R7") (pin "1") (pinfunction "1_1") (pintype "passive"))
      (node (ref "SW2") (pin "3") (pinfunction "3_3") (pintype "passive"))
      (node (ref "U1") (pin "10") (pinfunction "VDD_10") (pintype "power_in"))
      (node (ref "U1") (pin "61") (pinfunction "VDD_61") (pintype "power_in"))
      (node (ref "U2") (pin "5") (pinfunction "VOUT_5") (pintype "power_in"))
      (node (ref "U3") (pin "5") (pinfunction "VCC_5") (pintype "passive"))
      (node (ref "U3") (pin "8") (pinfunction "V3_8") (pintype "passive"))
      (node (ref "U5") (pin "13") (pinfunction "VDD_IO_13") (pintype "passive"))
    )
    (net (code "94") (name "VSYS") (class "Default")
      (node (ref "C4") (pin "2") (pinfunction "2_2") (pintype "passive"))
      (node (ref "D1") (pin "1") (pinfunction "K_1") (pintype "passive"))
      (node (ref "D2") (pin "1") (pinfunction "K_1") (pintype "passive"))
      (node (ref "J2") (pin "19") (pinfunction "39_19") (pintype "passive"))
      (node (ref "R14") (pin "1") (pinfunction "1_1") (pintype "passive"))
      (node (ref "U2") (pin "1") (pinfunction "IN_1") (pintype "power_in"))
    )
    (net (code "95") (name "unconnected-(P1-NC-PadR8)") (class "Default")
      (node (ref "P1") (pin "R8") (pinfunction "NC_R8") (pintype "passive+no_connect"))
    )
    (net (code "96") (name "unconnected-(P2-Pad4)") (class "Default")
      (node (ref "P2") (pin "4") (pinfunction "4_4") (pintype "passive"))
    )
    (net (code "97") (name "unconnected-(SW1-Pad2)") (class "Default")
      (node (ref "SW1") (pin "2") (pinfunction "2_2") (pintype "passive+no_connect"))
    )
    (net (code "98") (name "unconnected-(SW1-Pad4)") (class "Default")
      (node (ref "SW1") (pin "4") (pinfunction "4_4") (pintype "passive"))
    )
    (net (code "99") (name "unconnected-(SW2-Pad1)") (class "Default")
      (node (ref "SW2") (pin "1") (pinfunction "1_1") (pintype "passive+no_connect"))
    )
    (net (code "100") (name "unconnected-(SW2-Pad4)") (class "Default")
      (node (ref "SW2") (pin "4") (pinfunction "4_4") (pintype "passive+no_connect"))
    )
    (net (code "101") (name "unconnected-(U1-X32OUT-Pad60)") (class "Default")
      (node (ref "U1") (pin "60") (pinfunction "X32OUT_60") (pintype "bidirectional+no_connect"))
    )
    (net (code "102") (name "unconnected-(U1-XT32IN-Pad59)") (class "Default")
      (node (ref "U1") (pin "59") (pinfunction "XT32IN_59") (pintype "bidirectional+no_connect"))
    )
    (net (code "103") (name "unconnected-(U3-RTS-Pad4)") (class "Default")
      (node (ref "U3") (pin "4") (pinfunction "RTS_4") (pintype "passive+no_connect"))
    )
    (net (code "104") (name "unconnected-(U5-RXER-Pad21)") (class "Default")
      (node (ref "U5") (pin "21") (pinfunction "RXER_21") (pintype "passive+no_connect"))
    )
    (net (code "105") (name "unconnected-(U5-TXER{slash}FXSD-Pad1)") (class "Default")
      (node (ref "U5") (pin "1") (pinfunction "TXER/FXSD_1") (pintype "passive+no_connect"))
    )
  )
)
